# carte_bouton.net
KiCad netlist of a schematic drawn in EAGLE
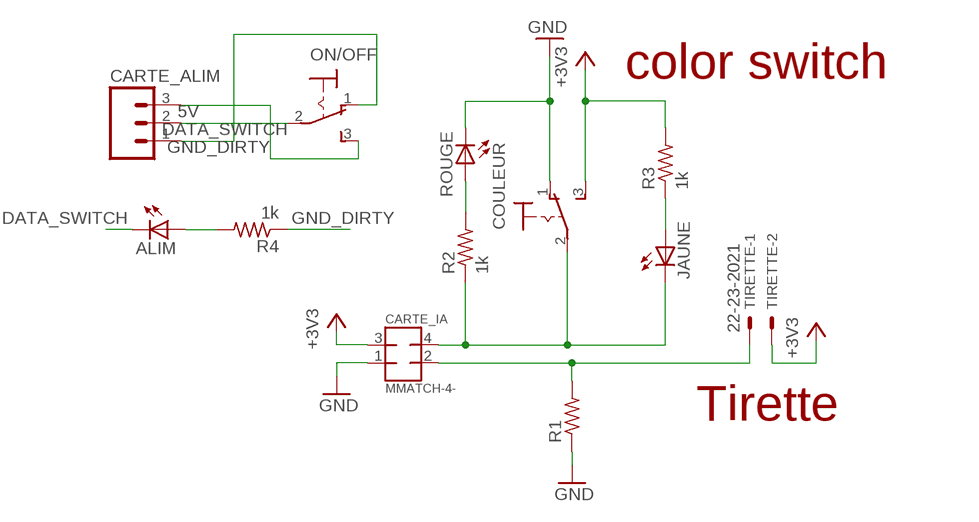
[diagram p0: schematic, sheet 1]

(export (version "E")
  (design (tool "Eeschema 10.0.6"))
  (components
    (comp (ref "ALIM")
      (value "LEDSML0805")
      (footprint "eagle-import:SML0805")
      (libsource (lib "eagle-import") (part "LEDSML0805"))
    )
    (comp (ref "CARTE_ALIM")
      (value "M03POLAR")
      (footprint "eagle-import:MOLEX-1X3")
      (libsource (lib "eagle-import") (part "M03POLAR"))
    )
    (comp (ref "CARTE_IA")
      (value "MMATCH-4-")
      (footprint "eagle-import:AMP-215079-4")
      (libsource (lib "eagle-import") (part "MMATCH-4-"))
    )
    (comp (ref "COULEUR")
      (value "320-916")
      (footprint "eagle-import:320-916")
      (libsource (lib "eagle-import") (part "320-916"))
    )
    (comp (ref "JAUNE")
      (value "LEDSML0805")
      (footprint "eagle-import:SML0805")
      (libsource (lib "eagle-import") (part "LEDSML0805"))
    )
    (comp (ref "ON/OFF")
      (value "320-916")
      (footprint "eagle-import:320-916")
      (libsource (lib "eagle-import") (part "320-916"))
    )
    (comp (ref "R1")
      (value "R-US_R0805")
      (footprint "eagle-import:R0805")
      (libsource (lib "eagle-import") (part "R-US_R0805"))
    )
    (comp (ref "R2")
      (value "1k")
      (footprint "eagle-import:M0805")
      (libsource (lib "eagle-import") (part "R-US_M0805"))
    )
    (comp (ref "R3")
      (value "1k")
      (footprint "eagle-import:M0805")
      (libsource (lib "eagle-import") (part "R-US_M0805"))
    )
    (comp (ref "R4")
      (value "1k")
      (footprint "eagle-import:M0805")
      (libsource (lib "eagle-import") (part "R-US_M0805"))
    )
    (comp (ref "ROUGE")
      (value "LEDSML0805")
      (footprint "eagle-import:SML0805")
      (libsource (lib "eagle-import") (part "LEDSML0805"))
    )
    (comp (ref "TIRETTE")
      (value "22-23-2021")
      (footprint "eagle-import:22-23-2021")
      (fields (field (name "MF") "MOLEX"))
      (libsource (lib "eagle-import") (part "22-23-2021"))
    )
  )
  (nets
    (net (code "1") (name "+3V3") (class "Default")
      (node (ref "CARTE_IA") (pin "3") (pinfunction "7_3") (pintype "bidirectional"))
      (node (ref "COULEUR") (pin "3") (pinfunction "S_3") (pintype "passive"))
      (node (ref "R3") (pin "2") (pinfunction "2_2") (pintype "passive"))
      (node (ref "TIRETTE") (pin "2") (pinfunction "S_2") (pintype "passive"))
    )
    (net (code "2") (name "/5V") (class "Default")
      (node (ref "CARTE_ALIM") (pin "3") (pinfunction "3_3") (pintype "passive"))
      (node (ref "ON/OFF") (pin "3") (pinfunction "S_3") (pintype "passive"))
    )
    (net (code "3") (name "/DATA_SWITCH") (class "Default")
      (node (ref "ALIM") (pin "C") (pinfunction "C_C") (pintype "passive"))
      (node (ref "CARTE_ALIM") (pin "2") (pinfunction "2_2") (pintype "passive"))
      (node (ref "ON/OFF") (pin "2") (pinfunction "P_2") (pintype "passive"))
    )
    (net (code "4") (name "/GND_DIRTY") (class "Default")
      (node (ref "CARTE_ALIM") (pin "1") (pinfunction "1_1") (pintype "passive"))
      (node (ref "ON/OFF") (pin "1") (pinfunction "O_1") (pintype "passive"))
      (node (ref "R4") (pin "1") (pinfunction "1_1") (pintype "passive"))
    )
    (net (code "5") (name "GND") (class "Default")
      (node (ref "CARTE_IA") (pin "1") (pinfunction "5_1") (pintype "bidirectional"))
      (node (ref "COULEUR") (pin "1") (pinfunction "O_1") (pintype "passive"))
      (node (ref "R1") (pin "1") (pinfunction "1_1") (pintype "passive"))
      (node (ref "ROUGE") (pin "C") (pinfunction "C_C") (pintype "passive"))
    )
    (net (code "6") (name "Net-(ALIM-PadA)") (class "Default")
      (node (ref "ALIM") (pin "A") (pinfunction "A_A") (pintype "passive"))
      (node (ref "R4") (pin "2") (pinfunction "2_2") (pintype "passive"))
    )
    (net (code "7") (name "Net-(CARTE_IA-6)") (class "Default")
      (node (ref "CARTE_IA") (pin "2") (pinfunction "6_2") (pintype "bidirectional"))
      (node (ref "R1") (pin "2") (pinfunction "2_2") (pintype "passive"))
      (node (ref "TIRETTE") (pin "1") (pinfunction "S_1") (pintype "passive"))
    )
    (net (code "8") (name "Net-(CARTE_IA-8)") (class "Default")
      (node (ref "CARTE_IA") (pin "4") (pinfunction "8_4") (pintype "bidirectional"))
      (node (ref "COULEUR") (pin "2") (pinfunction "P_2") (pintype "passive"))
      (node (ref "JAUNE") (pin "C") (pinfunction "C_C") (pintype "passive"))
      (node (ref "R2") (pin "1") (pinfunction "1_1") (pintype "passive"))
    )
    (net (code "9") (name "Net-(JAUNE-PadA)") (class "Default")
      (node (ref "JAUNE") (pin "A") (pinfunction "A_A") (pintype "passive"))
      (node (ref "R3") (pin "1") (pinfunction "1_1") (pintype "passive"))
    )
    (net (code "10") (name "Net-(R2-Pad2)") (class "Default")
      (node (ref "R2") (pin "2") (pinfunction "2_2") (pintype "passive"))
      (node (ref "ROUGE") (pin "A") (pinfunction "A_A") (pintype "passive"))
    )
  )
)
